# power_board_v2.net
KiCad netlist of a schematic drawn in EAGLE
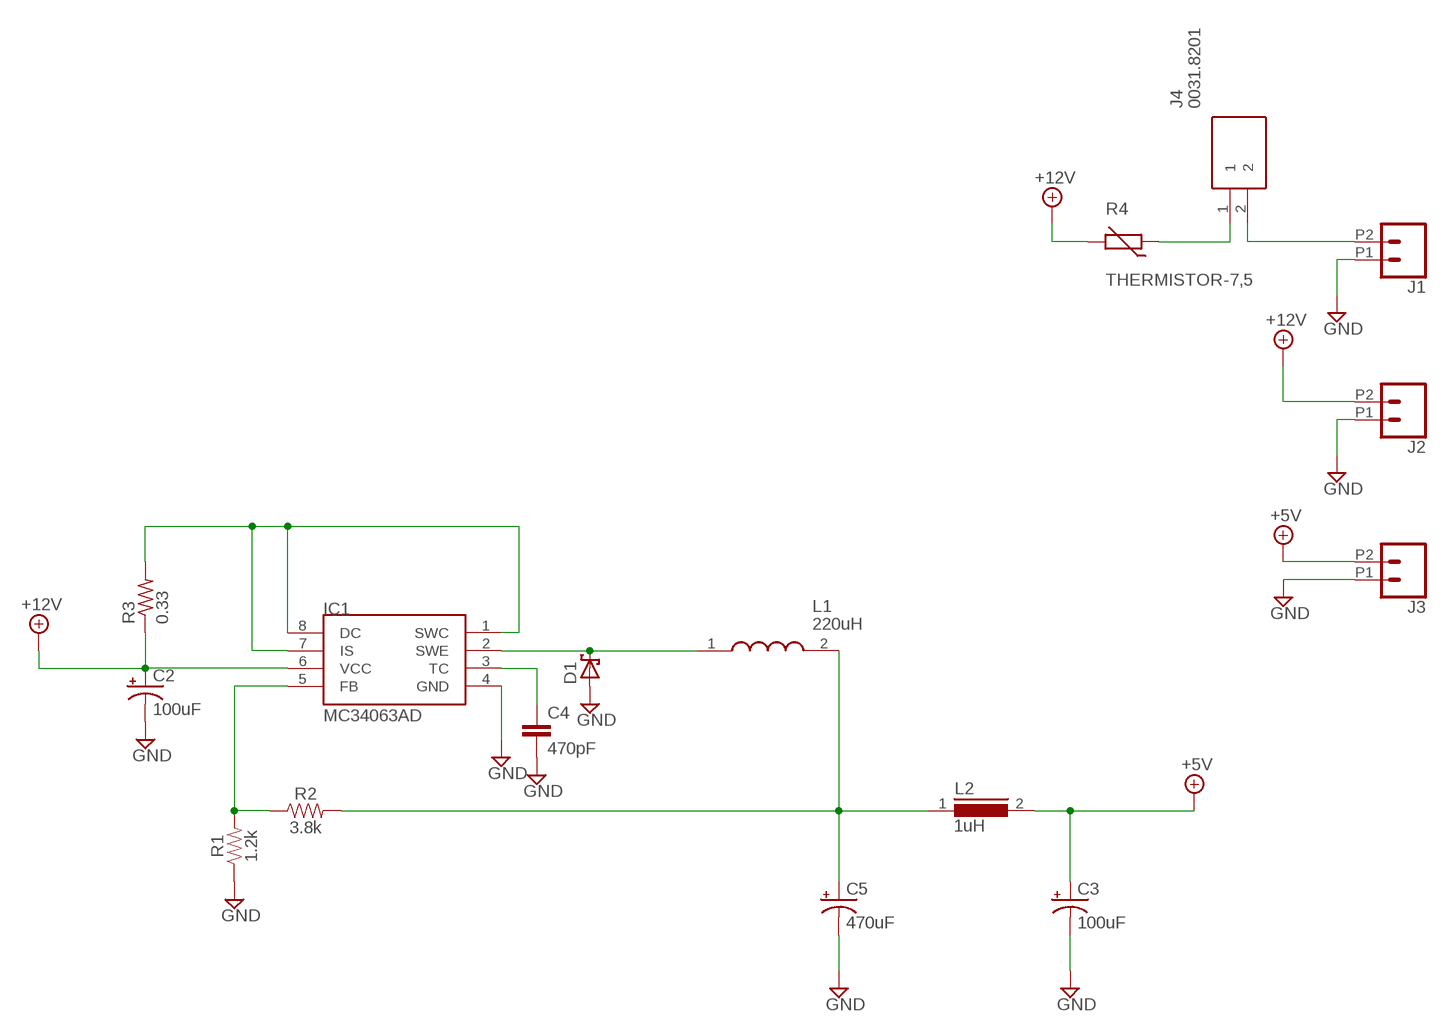
[diagram p0: schematic, sheet 1]

(export (version "E")
  (design (tool "Eeschema 10.0.6"))
  (components
    (comp (ref "C2")
      (value "100uF")
      (footprint "eagle-import:PANASONIC_D")
      (libsource (lib "eagle-import") (part "CPOL-USD"))
    )
    (comp (ref "C3")
      (value "100uF")
      (footprint "eagle-import:PANASONIC_D")
      (libsource (lib "eagle-import") (part "CPOL-USD"))
    )
    (comp (ref "C4")
      (value "470pF")
      (footprint "eagle-import:C0805")
      (libsource (lib "eagle-import") (part "C-EUC0805"))
    )
    (comp (ref "C5")
      (value "470uF")
      (footprint "eagle-import:PANASONIC_F")
      (libsource (lib "eagle-import") (part "CPOL-USF"))
    )
    (comp (ref "D1")
      (value "SCHOTTKY-DIODEDO41")
      (footprint "eagle-import:DO41-10")
      (libsource (lib "eagle-import") (part "SCHOTTKY-DIODEDO41"))
    )
    (comp (ref "IC1")
      (value "MC34063AD")
      (footprint "eagle-import:SOIC8")
      (libsource (lib "eagle-import") (part "MC34063AD"))
    )
    (comp (ref "J1")
      (value "CONN_02SCREWTERMINAL-6.35MM-2")
      (footprint "eagle-import:1X02_6.35_SCREWTERM")
      (libsource (lib "eagle-import") (part "CONN_02SCREWTERMINAL-6.35MM-2"))
    )
    (comp (ref "J2")
      (value "CONN_02SCREWTERMINAL-6.35MM-2")
      (footprint "eagle-import:1X02_6.35_SCREWTERM")
      (libsource (lib "eagle-import") (part "CONN_02SCREWTERMINAL-6.35MM-2"))
    )
    (comp (ref "J3")
      (value "CONN_02SCREWTERMINAL-6.35MM-2")
      (footprint "eagle-import:1X02_6.35_SCREWTERM")
      (libsource (lib "eagle-import") (part "CONN_02SCREWTERMINAL-6.35MM-2"))
    )
    (comp (ref "J4")
      (value "0031.8201")
      (footprint "eagle-import:0031.8201")
      (fields (field (name "RS_PART_NUMBER") "2508764386"))
      (libsource (lib "eagle-import") (part "0031.8201"))
    )
    (comp (ref "L1")
      (value "220uH")
      (footprint "eagle-import:WE-TI_809589")
      (fields
        (field (name "MANUFACTURER_PART_NUMBER") "744772220")
        (field (name "RS_PART_NUMBER") "4890043P")
      )
      (libsource (lib "eagle-import") (part "744772220"))
    )
    (comp (ref "L2")
      (value "1uH")
      (footprint "eagle-import:MICC12")
      (libsource (lib "eagle-import") (part "MICC12"))
    )
    (comp (ref "R1")
      (value "1.2k")
      (footprint "eagle-import:0805")
      (libsource (lib "eagle-import") (part "0.75OHM-0805-1/4W-1%"))
    )
    (comp (ref "R2")
      (value "3.8k")
      (footprint "eagle-import:0805")
      (libsource (lib "eagle-import") (part "0.75OHM-0805-1/4W-1%"))
    )
    (comp (ref "R3")
      (value "0.33")
      (footprint "eagle-import:R2512")
      (libsource (lib "eagle-import") (part "R-US_R2512"))
    )
    (comp (ref "R4")
      (value "THERMISTOR-7,5")
      (footprint "eagle-import:R-7,5")
      (libsource (lib "eagle-import") (part "THERMISTOR-7,5"))
    )
  )
  (nets
    (net (code "1") (name "+5V") (class "Default")
      (node (ref "C3") (pin "+") (pinfunction "+_+") (pintype "passive"))
      (node (ref "J3") (pin "P2") (pinfunction "1_P2") (pintype "passive"))
      (node (ref "L2") (pin "2") (pinfunction "2_2") (pintype "passive"))
    )
    (net (code "2") (name "+12V") (class "Default")
      (node (ref "C2") (pin "+") (pinfunction "+_+") (pintype "passive"))
      (node (ref "IC1") (pin "6") (pinfunction "VCC_6") (pintype "passive"))
      (node (ref "J2") (pin "P2") (pinfunction "1_P2") (pintype "passive"))
      (node (ref "R3") (pin "1") (pinfunction "1_1") (pintype "passive"))
      (node (ref "R4") (pin "2") (pinfunction "2_2") (pintype "passive"))
    )
    (net (code "3") (name "GND") (class "Default")
      (node (ref "C2") (pin "-") (pinfunction "-_-") (pintype "passive"))
      (node (ref "C3") (pin "-") (pinfunction "-_-") (pintype "passive"))
      (node (ref "C4") (pin "2") (pinfunction "2_2") (pintype "passive"))
      (node (ref "C5") (pin "-") (pinfunction "-_-") (pintype "passive"))
      (node (ref "D1") (pin "A") (pinfunction "A_A") (pintype "passive"))
      (node (ref "IC1") (pin "4") (pinfunction "GND_4") (pintype "passive"))
      (node (ref "J1") (pin "P1") (pinfunction "2_P1") (pintype "passive"))
      (node (ref "J2") (pin "P1") (pinfunction "2_P1") (pintype "passive"))
      (node (ref "J3") (pin "P1") (pinfunction "2_P1") (pintype "passive"))
      (node (ref "R1") (pin "1") (pinfunction "1_1") (pintype "passive"))
    )
    (net (code "4") (name "Net-(C5-Pad+)") (class "Default")
      (node (ref "C5") (pin "+") (pinfunction "+_+") (pintype "passive"))
      (node (ref "L1") (pin "2") (pinfunction "2_2") (pintype "bidirectional"))
      (node (ref "L2") (pin "1") (pinfunction "1_1") (pintype "passive"))
      (node (ref "R2") (pin "2") (pinfunction "2_2") (pintype "passive"))
    )
    (net (code "5") (name "Net-(IC1-DC)") (class "Default")
      (node (ref "IC1") (pin "1") (pinfunction "SWC_1") (pintype "passive"))
      (node (ref "IC1") (pin "7") (pinfunction "IS_7") (pintype "passive"))
      (node (ref "IC1") (pin "8") (pinfunction "DC_8") (pintype "passive"))
      (node (ref "R3") (pin "2") (pinfunction "2_2") (pintype "passive"))
    )
    (net (code "6") (name "Net-(IC1-FB)") (class "Default")
      (node (ref "IC1") (pin "5") (pinfunction "FB_5") (pintype "passive"))
      (node (ref "R1") (pin "2") (pinfunction "2_2") (pintype "passive"))
      (node (ref "R2") (pin "1") (pinfunction "1_1") (pintype "passive"))
    )
    (net (code "7") (name "Net-(IC1-SWE)") (class "Default")
      (node (ref "D1") (pin "C") (pinfunction "C_C") (pintype "passive"))
      (node (ref "IC1") (pin "2") (pinfunction "SWE_2") (pintype "passive"))
      (node (ref "L1") (pin "1") (pinfunction "1_1") (pintype "bidirectional"))
    )
    (net (code "8") (name "Net-(IC1-TC)") (class "Default")
      (node (ref "C4") (pin "1") (pinfunction "1_1") (pintype "passive"))
      (node (ref "IC1") (pin "3") (pinfunction "TC_3") (pintype "passive"))
    )
    (net (code "9") (name "Net-(J1-1)") (class "Default")
      (node (ref "J1") (pin "P2") (pinfunction "1_P2") (pintype "passive"))
      (node (ref "J4") (pin "2") (pinfunction "2_2") (pintype "bidirectional"))
    )
    (net (code "10") (name "Net-(J4-Pad1)") (class "Default")
      (node (ref "J4") (pin "1") (pinfunction "1_1") (pintype "bidirectional"))
      (node (ref "R4") (pin "1") (pinfunction "1_1") (pintype "passive"))
    )
  )
)
